# W051X.net
KiCad netlist of a schematic drawn in EAGLE
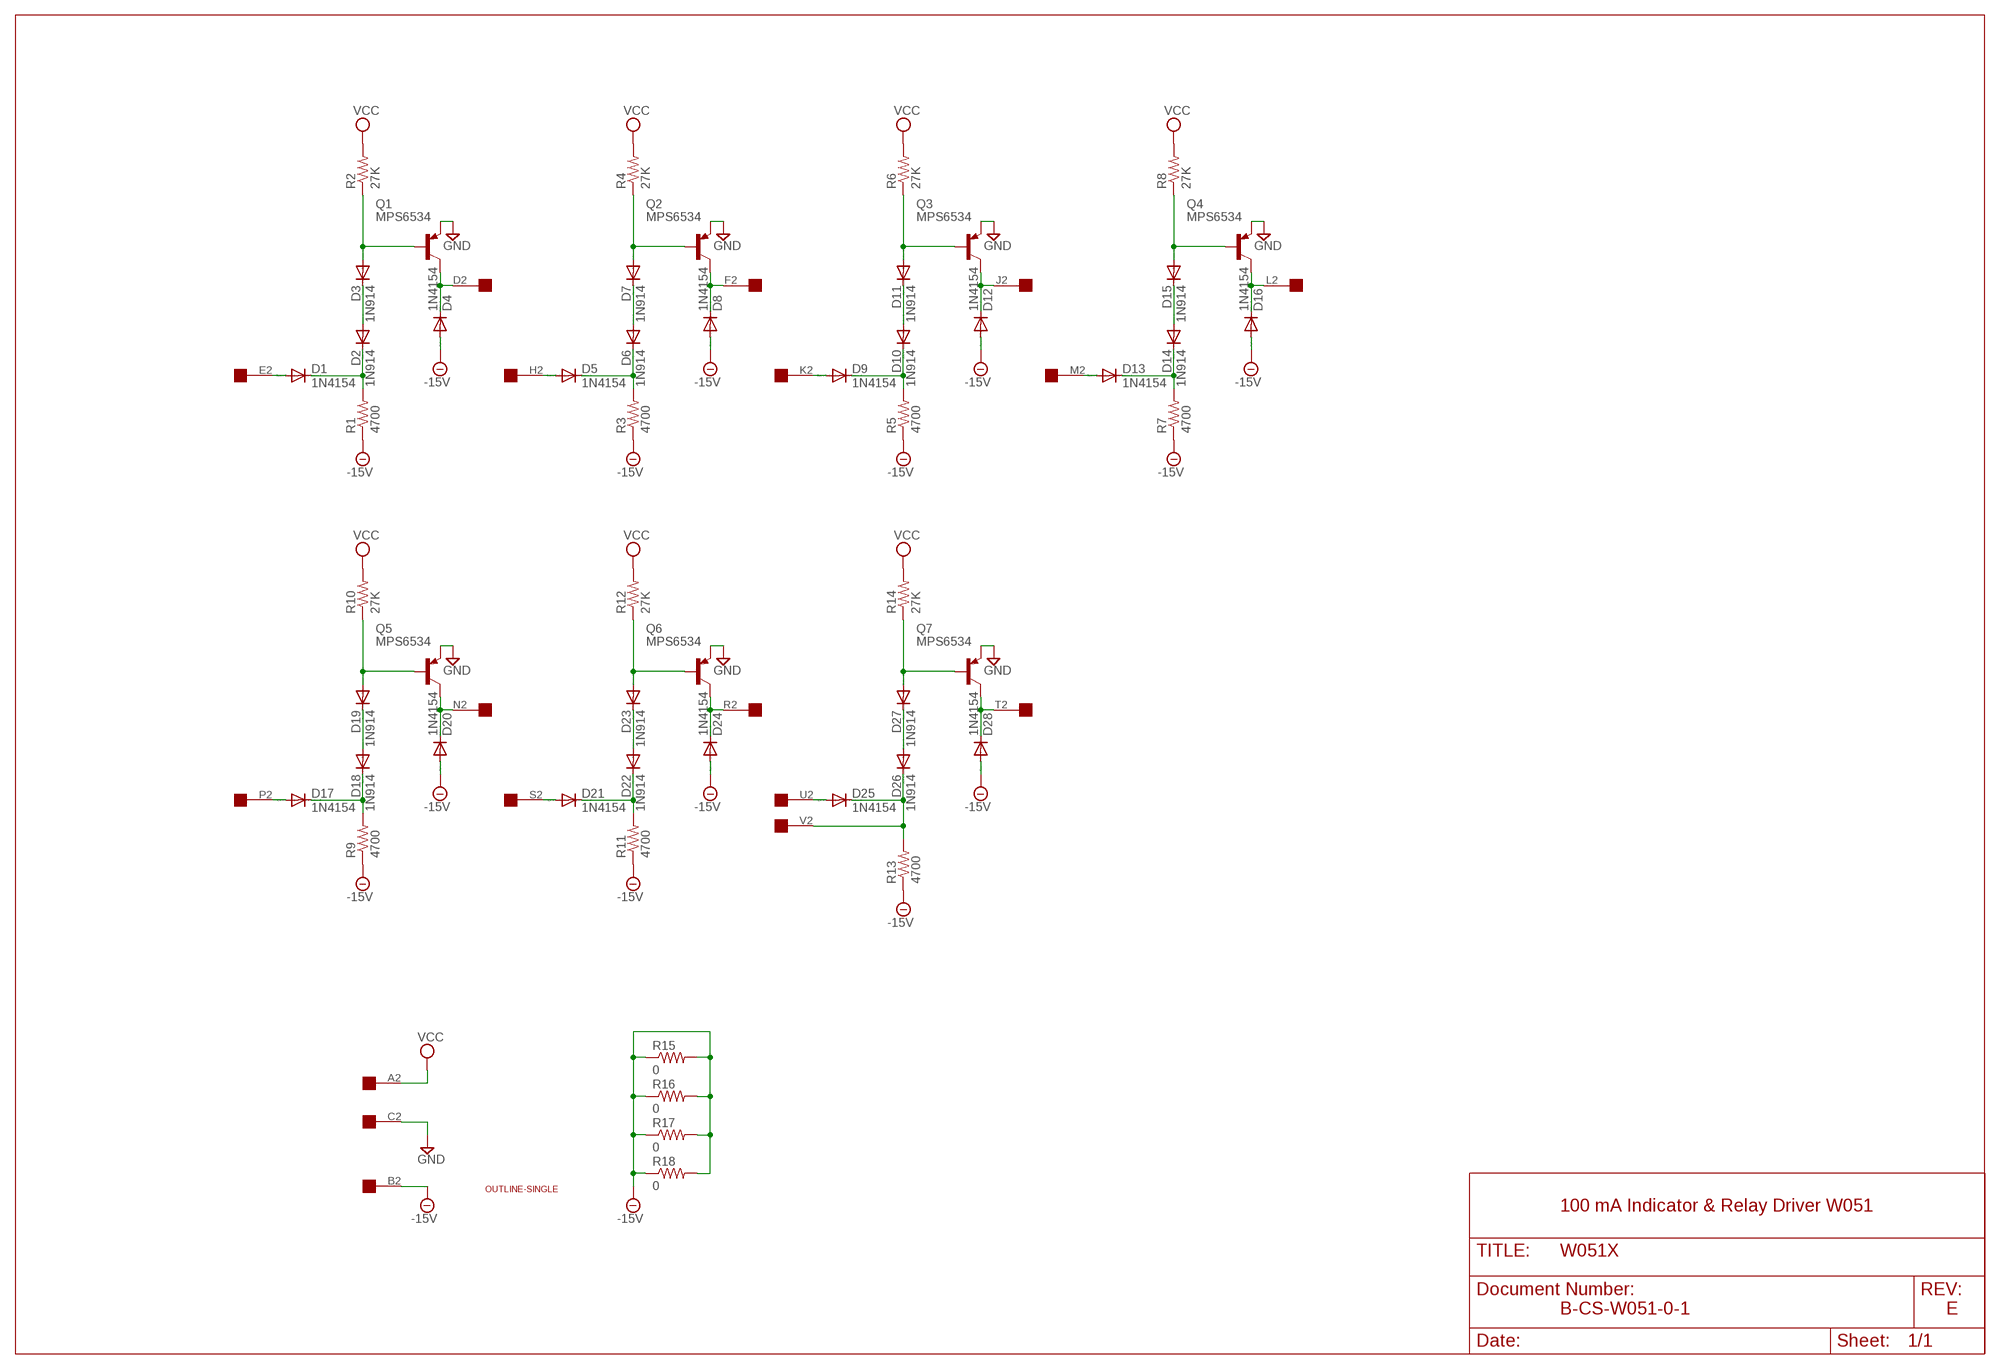
[diagram p0: schematic, sheet 1]

(export (version "E")
  (design (tool "Eeschema 10.0.6"))
  (components
    (comp (ref "D1")
      (value "1N4154")
      (footprint "eagle-import:DO35-10")
      (libsource (lib "eagle-import") (part "DIODE-DO35-10"))
    )
    (comp (ref "D2")
      (value "1N914")
      (footprint "eagle-import:DO35-10")
      (libsource (lib "eagle-import") (part "DIODE-DO35-10"))
    )
    (comp (ref "D3")
      (value "1N914")
      (footprint "eagle-import:DO35-10")
      (libsource (lib "eagle-import") (part "DIODE-DO35-10"))
    )
    (comp (ref "D4")
      (value "1N4154")
      (footprint "eagle-import:DO35-10")
      (libsource (lib "eagle-import") (part "DIODE-DO35-10"))
    )
    (comp (ref "D5")
      (value "1N4154")
      (footprint "eagle-import:DO35-10")
      (libsource (lib "eagle-import") (part "DIODE-DO35-10"))
    )
    (comp (ref "D6")
      (value "1N914")
      (footprint "eagle-import:DO35-10")
      (libsource (lib "eagle-import") (part "DIODE-DO35-10"))
    )
    (comp (ref "D7")
      (value "1N914")
      (footprint "eagle-import:DO35-10")
      (libsource (lib "eagle-import") (part "DIODE-DO35-10"))
    )
    (comp (ref "D8")
      (value "1N4154")
      (footprint "eagle-import:DO35-10")
      (libsource (lib "eagle-import") (part "DIODE-DO35-10"))
    )
    (comp (ref "D9")
      (value "1N4154")
      (footprint "eagle-import:DO35-10")
      (libsource (lib "eagle-import") (part "DIODE-DO35-10"))
    )
    (comp (ref "D10")
      (value "1N914")
      (footprint "eagle-import:DO35-10")
      (libsource (lib "eagle-import") (part "DIODE-DO35-10"))
    )
    (comp (ref "D11")
      (value "1N914")
      (footprint "eagle-import:DO35-10")
      (libsource (lib "eagle-import") (part "DIODE-DO35-10"))
    )
    (comp (ref "D12")
      (value "1N4154")
      (footprint "eagle-import:DO35-10")
      (libsource (lib "eagle-import") (part "DIODE-DO35-10"))
    )
    (comp (ref "D13")
      (value "1N4154")
      (footprint "eagle-import:DO35-10")
      (libsource (lib "eagle-import") (part "DIODE-DO35-10"))
    )
    (comp (ref "D14")
      (value "1N914")
      (footprint "eagle-import:DO35-10")
      (libsource (lib "eagle-import") (part "DIODE-DO35-10"))
    )
    (comp (ref "D15")
      (value "1N914")
      (footprint "eagle-import:DO35-10")
      (libsource (lib "eagle-import") (part "DIODE-DO35-10"))
    )
    (comp (ref "D16")
      (value "1N4154")
      (footprint "eagle-import:DO35-10")
      (libsource (lib "eagle-import") (part "DIODE-DO35-10"))
    )
    (comp (ref "D17")
      (value "1N4154")
      (footprint "eagle-import:DO35-10")
      (libsource (lib "eagle-import") (part "DIODE-DO35-10"))
    )
    (comp (ref "D18")
      (value "1N914")
      (footprint "eagle-import:DO35-10")
      (libsource (lib "eagle-import") (part "DIODE-DO35-10"))
    )
    (comp (ref "D19")
      (value "1N914")
      (footprint "eagle-import:DO35-10")
      (libsource (lib "eagle-import") (part "DIODE-DO35-10"))
    )
    (comp (ref "D20")
      (value "1N4154")
      (footprint "eagle-import:DO35-10")
      (libsource (lib "eagle-import") (part "DIODE-DO35-10"))
    )
    (comp (ref "D21")
      (value "1N4154")
      (footprint "eagle-import:DO35-10")
      (libsource (lib "eagle-import") (part "DIODE-DO35-10"))
    )
    (comp (ref "D22")
      (value "1N914")
      (footprint "eagle-import:DO35-10")
      (libsource (lib "eagle-import") (part "DIODE-DO35-10"))
    )
    (comp (ref "D23")
      (value "1N914")
      (footprint "eagle-import:DO35-10")
      (libsource (lib "eagle-import") (part "DIODE-DO35-10"))
    )
    (comp (ref "D24")
      (value "1N4154")
      (footprint "eagle-import:DO35-10")
      (libsource (lib "eagle-import") (part "DIODE-DO35-10"))
    )
    (comp (ref "D25")
      (value "1N4154")
      (footprint "eagle-import:DO35-10")
      (libsource (lib "eagle-import") (part "DIODE-DO35-10"))
    )
    (comp (ref "D26")
      (value "1N914")
      (footprint "eagle-import:DO35-10")
      (libsource (lib "eagle-import") (part "DIODE-DO35-10"))
    )
    (comp (ref "D27")
      (value "1N914")
      (footprint "eagle-import:DO35-10")
      (libsource (lib "eagle-import") (part "DIODE-DO35-10"))
    )
    (comp (ref "D28")
      (value "1N4154")
      (footprint "eagle-import:DO35-10")
      (libsource (lib "eagle-import") (part "DIODE-DO35-10"))
    )
    (comp (ref "Q1")
      (value "MPS6534")
      (footprint "eagle-import:TO5")
      (libsource (lib "eagle-import") (part "-PNP-TO5"))
    )
    (comp (ref "Q2")
      (value "MPS6534")
      (footprint "eagle-import:TO5")
      (libsource (lib "eagle-import") (part "-PNP-TO5"))
    )
    (comp (ref "Q3")
      (value "MPS6534")
      (footprint "eagle-import:TO5")
      (libsource (lib "eagle-import") (part "-PNP-TO5"))
    )
    (comp (ref "Q4")
      (value "MPS6534")
      (footprint "eagle-import:TO5")
      (libsource (lib "eagle-import") (part "-PNP-TO5"))
    )
    (comp (ref "Q5")
      (value "MPS6534")
      (footprint "eagle-import:TO5")
      (libsource (lib "eagle-import") (part "-PNP-TO5"))
    )
    (comp (ref "Q6")
      (value "MPS6534")
      (footprint "eagle-import:TO5")
      (libsource (lib "eagle-import") (part "-PNP-TO5"))
    )
    (comp (ref "Q7")
      (value "MPS6534")
      (footprint "eagle-import:TO5")
      (libsource (lib "eagle-import") (part "-PNP-TO5"))
    )
    (comp (ref "R1")
      (value "4700")
      (footprint "eagle-import:0207_10")
      (libsource (lib "eagle-import") (part "R-US_0207/10"))
    )
    (comp (ref "R2")
      (value "27K")
      (footprint "eagle-import:0207_10")
      (libsource (lib "eagle-import") (part "R-US_0207/10"))
    )
    (comp (ref "R3")
      (value "4700")
      (footprint "eagle-import:0207_10")
      (libsource (lib "eagle-import") (part "R-US_0207/10"))
    )
    (comp (ref "R4")
      (value "27K")
      (footprint "eagle-import:0207_10")
      (libsource (lib "eagle-import") (part "R-US_0207/10"))
    )
    (comp (ref "R5")
      (value "4700")
      (footprint "eagle-import:0207_10")
      (libsource (lib "eagle-import") (part "R-US_0207/10"))
    )
    (comp (ref "R6")
      (value "27K")
      (footprint "eagle-import:0207_10")
      (libsource (lib "eagle-import") (part "R-US_0207/10"))
    )
    (comp (ref "R7")
      (value "4700")
      (footprint "eagle-import:0207_10")
      (libsource (lib "eagle-import") (part "R-US_0207/10"))
    )
    (comp (ref "R8")
      (value "27K")
      (footprint "eagle-import:0207_10")
      (libsource (lib "eagle-import") (part "R-US_0207/10"))
    )
    (comp (ref "R9")
      (value "4700")
      (footprint "eagle-import:0207_10")
      (libsource (lib "eagle-import") (part "R-US_0207/10"))
    )
    (comp (ref "R10")
      (value "27K")
      (footprint "eagle-import:0207_10")
      (libsource (lib "eagle-import") (part "R-US_0207/10"))
    )
    (comp (ref "R11")
      (value "4700")
      (footprint "eagle-import:0207_10")
      (libsource (lib "eagle-import") (part "R-US_0207/10"))
    )
    (comp (ref "R12")
      (value "27K")
      (footprint "eagle-import:0207_10")
      (libsource (lib "eagle-import") (part "R-US_0207/10"))
    )
    (comp (ref "R13")
      (value "4700")
      (footprint "eagle-import:0207_10")
      (libsource (lib "eagle-import") (part "R-US_0207/10"))
    )
    (comp (ref "R14")
      (value "27K")
      (footprint "eagle-import:0207_10")
      (libsource (lib "eagle-import") (part "R-US_0207/10"))
    )
    (comp (ref "R15")
      (value "0")
      (footprint "eagle-import:0207_10")
      (libsource (lib "eagle-import") (part "R-US_0207/10"))
    )
    (comp (ref "R16")
      (value "0")
      (footprint "eagle-import:0207_10")
      (libsource (lib "eagle-import") (part "R-US_0207/10"))
    )
    (comp (ref "R17")
      (value "0")
      (footprint "eagle-import:0207_10")
      (libsource (lib "eagle-import") (part "R-US_0207/10"))
    )
    (comp (ref "R18")
      (value "0")
      (footprint "eagle-import:0207_10")
      (libsource (lib "eagle-import") (part "R-US_0207/10"))
    )
    (comp (ref "U$1")
      (value "OUTLINE-SINGLE")
      (footprint "eagle-import:SINGLE")
      (libsource (lib "eagle-import") (part "OUTLINE-SINGLE"))
    )
    (comp (ref "U$2")
      (value "EDGE-1")
      (footprint "eagle-import:EDGE-CON1")
      (libsource (lib "eagle-import") (part "EDGE-1"))
    )
  )
  (nets
    (net (code "1") (name "-15V") (class "Default")
      (node (ref "D12") (pin "A") (pinfunction "A_A") (pintype "passive"))
      (node (ref "D16") (pin "A") (pinfunction "A_A") (pintype "passive"))
      (node (ref "D20") (pin "A") (pinfunction "A_A") (pintype "passive"))
      (node (ref "D24") (pin "A") (pinfunction "A_A") (pintype "passive"))
      (node (ref "D28") (pin "A") (pinfunction "A_A") (pintype "passive"))
      (node (ref "D4") (pin "A") (pinfunction "A_A") (pintype "passive"))
      (node (ref "D8") (pin "A") (pinfunction "A_A") (pintype "passive"))
      (node (ref "R1") (pin "1") (pinfunction "1_1") (pintype "passive"))
      (node (ref "R11") (pin "1") (pinfunction "1_1") (pintype "passive"))
      (node (ref "R13") (pin "1") (pinfunction "1_1") (pintype "passive"))
      (node (ref "R15") (pin "1") (pinfunction "1_1") (pintype "passive"))
      (node (ref "R15") (pin "2") (pinfunction "2_2") (pintype "passive"))
      (node (ref "R16") (pin "1") (pinfunction "1_1") (pintype "passive"))
      (node (ref "R16") (pin "2") (pinfunction "2_2") (pintype "passive"))
      (node (ref "R17") (pin "1") (pinfunction "1_1") (pintype "passive"))
      (node (ref "R17") (pin "2") (pinfunction "2_2") (pintype "passive"))
      (node (ref "R18") (pin "1") (pinfunction "1_1") (pintype "passive"))
      (node (ref "R18") (pin "2") (pinfunction "2_2") (pintype "passive"))
      (node (ref "R3") (pin "1") (pinfunction "1_1") (pintype "passive"))
      (node (ref "R5") (pin "1") (pinfunction "1_1") (pintype "passive"))
      (node (ref "R7") (pin "1") (pinfunction "1_1") (pintype "passive"))
      (node (ref "R9") (pin "1") (pinfunction "1_1") (pintype "passive"))
      (node (ref "U$2") (pin "B2") (pinfunction "1_B2") (pintype "bidirectional"))
    )
    (net (code "2") (name "GND") (class "Default")
      (node (ref "Q1") (pin "1") (pinfunction "E_1") (pintype "passive"))
      (node (ref "Q2") (pin "1") (pinfunction "E_1") (pintype "passive"))
      (node (ref "Q3") (pin "1") (pinfunction "E_1") (pintype "passive"))
      (node (ref "Q4") (pin "1") (pinfunction "E_1") (pintype "passive"))
      (node (ref "Q5") (pin "1") (pinfunction "E_1") (pintype "passive"))
      (node (ref "Q6") (pin "1") (pinfunction "E_1") (pintype "passive"))
      (node (ref "Q7") (pin "1") (pinfunction "E_1") (pintype "passive"))
      (node (ref "U$2") (pin "C2") (pinfunction "1_C2") (pintype "bidirectional"))
    )
    (net (code "3") (name "Net-(D1-PadC)") (class "Default")
      (node (ref "D1") (pin "C") (pinfunction "C_C") (pintype "passive"))
      (node (ref "D2") (pin "C") (pinfunction "C_C") (pintype "passive"))
      (node (ref "R1") (pin "2") (pinfunction "2_2") (pintype "passive"))
    )
    (net (code "4") (name "Net-(D2-PadA)") (class "Default")
      (node (ref "D2") (pin "A") (pinfunction "A_A") (pintype "passive"))
      (node (ref "D3") (pin "C") (pinfunction "C_C") (pintype "passive"))
    )
    (net (code "5") (name "Net-(D5-PadC)") (class "Default")
      (node (ref "D5") (pin "C") (pinfunction "C_C") (pintype "passive"))
      (node (ref "D6") (pin "C") (pinfunction "C_C") (pintype "passive"))
      (node (ref "R3") (pin "2") (pinfunction "2_2") (pintype "passive"))
    )
    (net (code "6") (name "Net-(D6-PadA)") (class "Default")
      (node (ref "D6") (pin "A") (pinfunction "A_A") (pintype "passive"))
      (node (ref "D7") (pin "C") (pinfunction "C_C") (pintype "passive"))
    )
    (net (code "7") (name "Net-(D10-PadA)") (class "Default")
      (node (ref "D10") (pin "A") (pinfunction "A_A") (pintype "passive"))
      (node (ref "D11") (pin "C") (pinfunction "C_C") (pintype "passive"))
    )
    (net (code "8") (name "Net-(D10-PadC)") (class "Default")
      (node (ref "D10") (pin "C") (pinfunction "C_C") (pintype "passive"))
      (node (ref "D9") (pin "C") (pinfunction "C_C") (pintype "passive"))
      (node (ref "R5") (pin "2") (pinfunction "2_2") (pintype "passive"))
    )
    (net (code "9") (name "Net-(D13-PadC)") (class "Default")
      (node (ref "D13") (pin "C") (pinfunction "C_C") (pintype "passive"))
      (node (ref "D14") (pin "C") (pinfunction "C_C") (pintype "passive"))
      (node (ref "R7") (pin "2") (pinfunction "2_2") (pintype "passive"))
    )
    (net (code "10") (name "Net-(D14-PadA)") (class "Default")
      (node (ref "D14") (pin "A") (pinfunction "A_A") (pintype "passive"))
      (node (ref "D15") (pin "C") (pinfunction "C_C") (pintype "passive"))
    )
    (net (code "11") (name "Net-(D17-PadC)") (class "Default")
      (node (ref "D17") (pin "C") (pinfunction "C_C") (pintype "passive"))
      (node (ref "D18") (pin "C") (pinfunction "C_C") (pintype "passive"))
      (node (ref "R9") (pin "2") (pinfunction "2_2") (pintype "passive"))
    )
    (net (code "12") (name "Net-(D18-PadA)") (class "Default")
      (node (ref "D18") (pin "A") (pinfunction "A_A") (pintype "passive"))
      (node (ref "D19") (pin "C") (pinfunction "C_C") (pintype "passive"))
    )
    (net (code "13") (name "Net-(D21-PadC)") (class "Default")
      (node (ref "D21") (pin "C") (pinfunction "C_C") (pintype "passive"))
      (node (ref "D22") (pin "C") (pinfunction "C_C") (pintype "passive"))
      (node (ref "R11") (pin "2") (pinfunction "2_2") (pintype "passive"))
    )
    (net (code "14") (name "Net-(D22-PadA)") (class "Default")
      (node (ref "D22") (pin "A") (pinfunction "A_A") (pintype "passive"))
      (node (ref "D23") (pin "C") (pinfunction "C_C") (pintype "passive"))
    )
    (net (code "15") (name "Net-(D26-PadA)") (class "Default")
      (node (ref "D26") (pin "A") (pinfunction "A_A") (pintype "passive"))
      (node (ref "D27") (pin "C") (pinfunction "C_C") (pintype "passive"))
    )
    (net (code "16") (name "Net-(Q1-B)") (class "Default")
      (node (ref "D3") (pin "A") (pinfunction "A_A") (pintype "passive"))
      (node (ref "Q1") (pin "2") (pinfunction "B_2") (pintype "passive"))
      (node (ref "R2") (pin "1") (pinfunction "1_1") (pintype "passive"))
    )
    (net (code "17") (name "Net-(Q1-C)") (class "Default")
      (node (ref "D4") (pin "C") (pinfunction "C_C") (pintype "passive"))
      (node (ref "Q1") (pin "3") (pinfunction "C_3") (pintype "passive"))
      (node (ref "U$2") (pin "D2") (pinfunction "1_D2") (pintype "bidirectional"))
    )
    (net (code "18") (name "Net-(Q2-B)") (class "Default")
      (node (ref "D7") (pin "A") (pinfunction "A_A") (pintype "passive"))
      (node (ref "Q2") (pin "2") (pinfunction "B_2") (pintype "passive"))
      (node (ref "R4") (pin "1") (pinfunction "1_1") (pintype "passive"))
    )
    (net (code "19") (name "Net-(Q2-C)") (class "Default")
      (node (ref "D8") (pin "C") (pinfunction "C_C") (pintype "passive"))
      (node (ref "Q2") (pin "3") (pinfunction "C_3") (pintype "passive"))
      (node (ref "U$2") (pin "F2") (pinfunction "1_F2") (pintype "bidirectional"))
    )
    (net (code "20") (name "Net-(Q3-B)") (class "Default")
      (node (ref "D11") (pin "A") (pinfunction "A_A") (pintype "passive"))
      (node (ref "Q3") (pin "2") (pinfunction "B_2") (pintype "passive"))
      (node (ref "R6") (pin "1") (pinfunction "1_1") (pintype "passive"))
    )
    (net (code "21") (name "Net-(Q3-C)") (class "Default")
      (node (ref "D12") (pin "C") (pinfunction "C_C") (pintype "passive"))
      (node (ref "Q3") (pin "3") (pinfunction "C_3") (pintype "passive"))
      (node (ref "U$2") (pin "J2") (pinfunction "1_J2") (pintype "bidirectional"))
    )
    (net (code "22") (name "Net-(Q4-B)") (class "Default")
      (node (ref "D15") (pin "A") (pinfunction "A_A") (pintype "passive"))
      (node (ref "Q4") (pin "2") (pinfunction "B_2") (pintype "passive"))
      (node (ref "R8") (pin "1") (pinfunction "1_1") (pintype "passive"))
    )
    (net (code "23") (name "Net-(Q4-C)") (class "Default")
      (node (ref "D16") (pin "C") (pinfunction "C_C") (pintype "passive"))
      (node (ref "Q4") (pin "3") (pinfunction "C_3") (pintype "passive"))
      (node (ref "U$2") (pin "L2") (pinfunction "1_L2") (pintype "bidirectional"))
    )
    (net (code "24") (name "Net-(Q5-B)") (class "Default")
      (node (ref "D19") (pin "A") (pinfunction "A_A") (pintype "passive"))
      (node (ref "Q5") (pin "2") (pinfunction "B_2") (pintype "passive"))
      (node (ref "R10") (pin "1") (pinfunction "1_1") (pintype "passive"))
    )
    (net (code "25") (name "Net-(Q5-C)") (class "Default")
      (node (ref "D20") (pin "C") (pinfunction "C_C") (pintype "passive"))
      (node (ref "Q5") (pin "3") (pinfunction "C_3") (pintype "passive"))
      (node (ref "U$2") (pin "N2") (pinfunction "1_N2") (pintype "bidirectional"))
    )
    (net (code "26") (name "Net-(Q6-B)") (class "Default")
      (node (ref "D23") (pin "A") (pinfunction "A_A") (pintype "passive"))
      (node (ref "Q6") (pin "2") (pinfunction "B_2") (pintype "passive"))
      (node (ref "R12") (pin "1") (pinfunction "1_1") (pintype "passive"))
    )
    (net (code "27") (name "Net-(Q6-C)") (class "Default")
      (node (ref "D24") (pin "C") (pinfunction "C_C") (pintype "passive"))
      (node (ref "Q6") (pin "3") (pinfunction "C_3") (pintype "passive"))
      (node (ref "U$2") (pin "R2") (pinfunction "1_R2") (pintype "bidirectional"))
    )
    (net (code "28") (name "Net-(Q7-B)") (class "Default")
      (node (ref "D27") (pin "A") (pinfunction "A_A") (pintype "passive"))
      (node (ref "Q7") (pin "2") (pinfunction "B_2") (pintype "passive"))
      (node (ref "R14") (pin "1") (pinfunction "1_1") (pintype "passive"))
    )
    (net (code "29") (name "Net-(Q7-C)") (class "Default")
      (node (ref "D28") (pin "C") (pinfunction "C_C") (pintype "passive"))
      (node (ref "Q7") (pin "3") (pinfunction "C_3") (pintype "passive"))
      (node (ref "U$2") (pin "T2") (pinfunction "1_T2") (pintype "bidirectional"))
    )
    (net (code "30") (name "Net-(U$2E-1)") (class "Default")
      (node (ref "D1") (pin "A") (pinfunction "A_A") (pintype "passive"))
      (node (ref "U$2") (pin "E2") (pinfunction "1_E2") (pintype "bidirectional"))
    )
    (net (code "31") (name "Net-(U$2G-1)") (class "Default")
      (node (ref "D5") (pin "A") (pinfunction "A_A") (pintype "passive"))
      (node (ref "U$2") (pin "H2") (pinfunction "1_H2") (pintype "bidirectional"))
    )
    (net (code "32") (name "Net-(U$2I-1)") (class "Default")
      (node (ref "D9") (pin "A") (pinfunction "A_A") (pintype "passive"))
      (node (ref "U$2") (pin "K2") (pinfunction "1_K2") (pintype "bidirectional"))
    )
    (net (code "33") (name "Net-(U$2K-1)") (class "Default")
      (node (ref "D13") (pin "A") (pinfunction "A_A") (pintype "passive"))
      (node (ref "U$2") (pin "M2") (pinfunction "1_M2") (pintype "bidirectional"))
    )
    (net (code "34") (name "Net-(U$2M-1)") (class "Default")
      (node (ref "D17") (pin "A") (pinfunction "A_A") (pintype "passive"))
      (node (ref "U$2") (pin "P2") (pinfunction "1_P2") (pintype "bidirectional"))
    )
    (net (code "35") (name "Net-(U$2O-1)") (class "Default")
      (node (ref "D21") (pin "A") (pinfunction "A_A") (pintype "passive"))
      (node (ref "U$2") (pin "S2") (pinfunction "1_S2") (pintype "bidirectional"))
    )
    (net (code "36") (name "Net-(U$2Q-1)") (class "Default")
      (node (ref "D25") (pin "A") (pinfunction "A_A") (pintype "passive"))
      (node (ref "U$2") (pin "U2") (pinfunction "1_U2") (pintype "bidirectional"))
    )
    (net (code "37") (name "Net-(U$2R-1)") (class "Default")
      (node (ref "D25") (pin "C") (pinfunction "C_C") (pintype "passive"))
      (node (ref "D26") (pin "C") (pinfunction "C_C") (pintype "passive"))
      (node (ref "R13") (pin "2") (pinfunction "2_2") (pintype "passive"))
      (node (ref "U$2") (pin "V2") (pinfunction "1_V2") (pintype "bidirectional"))
    )
    (net (code "38") (name "VCC") (class "Default")
      (node (ref "R10") (pin "2") (pinfunction "2_2") (pintype "passive"))
      (node (ref "R12") (pin "2") (pinfunction "2_2") (pintype "passive"))
      (node (ref "R14") (pin "2") (pinfunction "2_2") (pintype "passive"))
      (node (ref "R2") (pin "2") (pinfunction "2_2") (pintype "passive"))
      (node (ref "R4") (pin "2") (pinfunction "2_2") (pintype "passive"))
      (node (ref "R6") (pin "2") (pinfunction "2_2") (pintype "passive"))
      (node (ref "R8") (pin "2") (pinfunction "2_2") (pintype "passive"))
      (node (ref "U$2") (pin "A2") (pinfunction "1_A2") (pintype "bidirectional"))
    )
  )
)
